# MainSchematic_F1.net
KiCad netlist of a schematic drawn in EAGLE
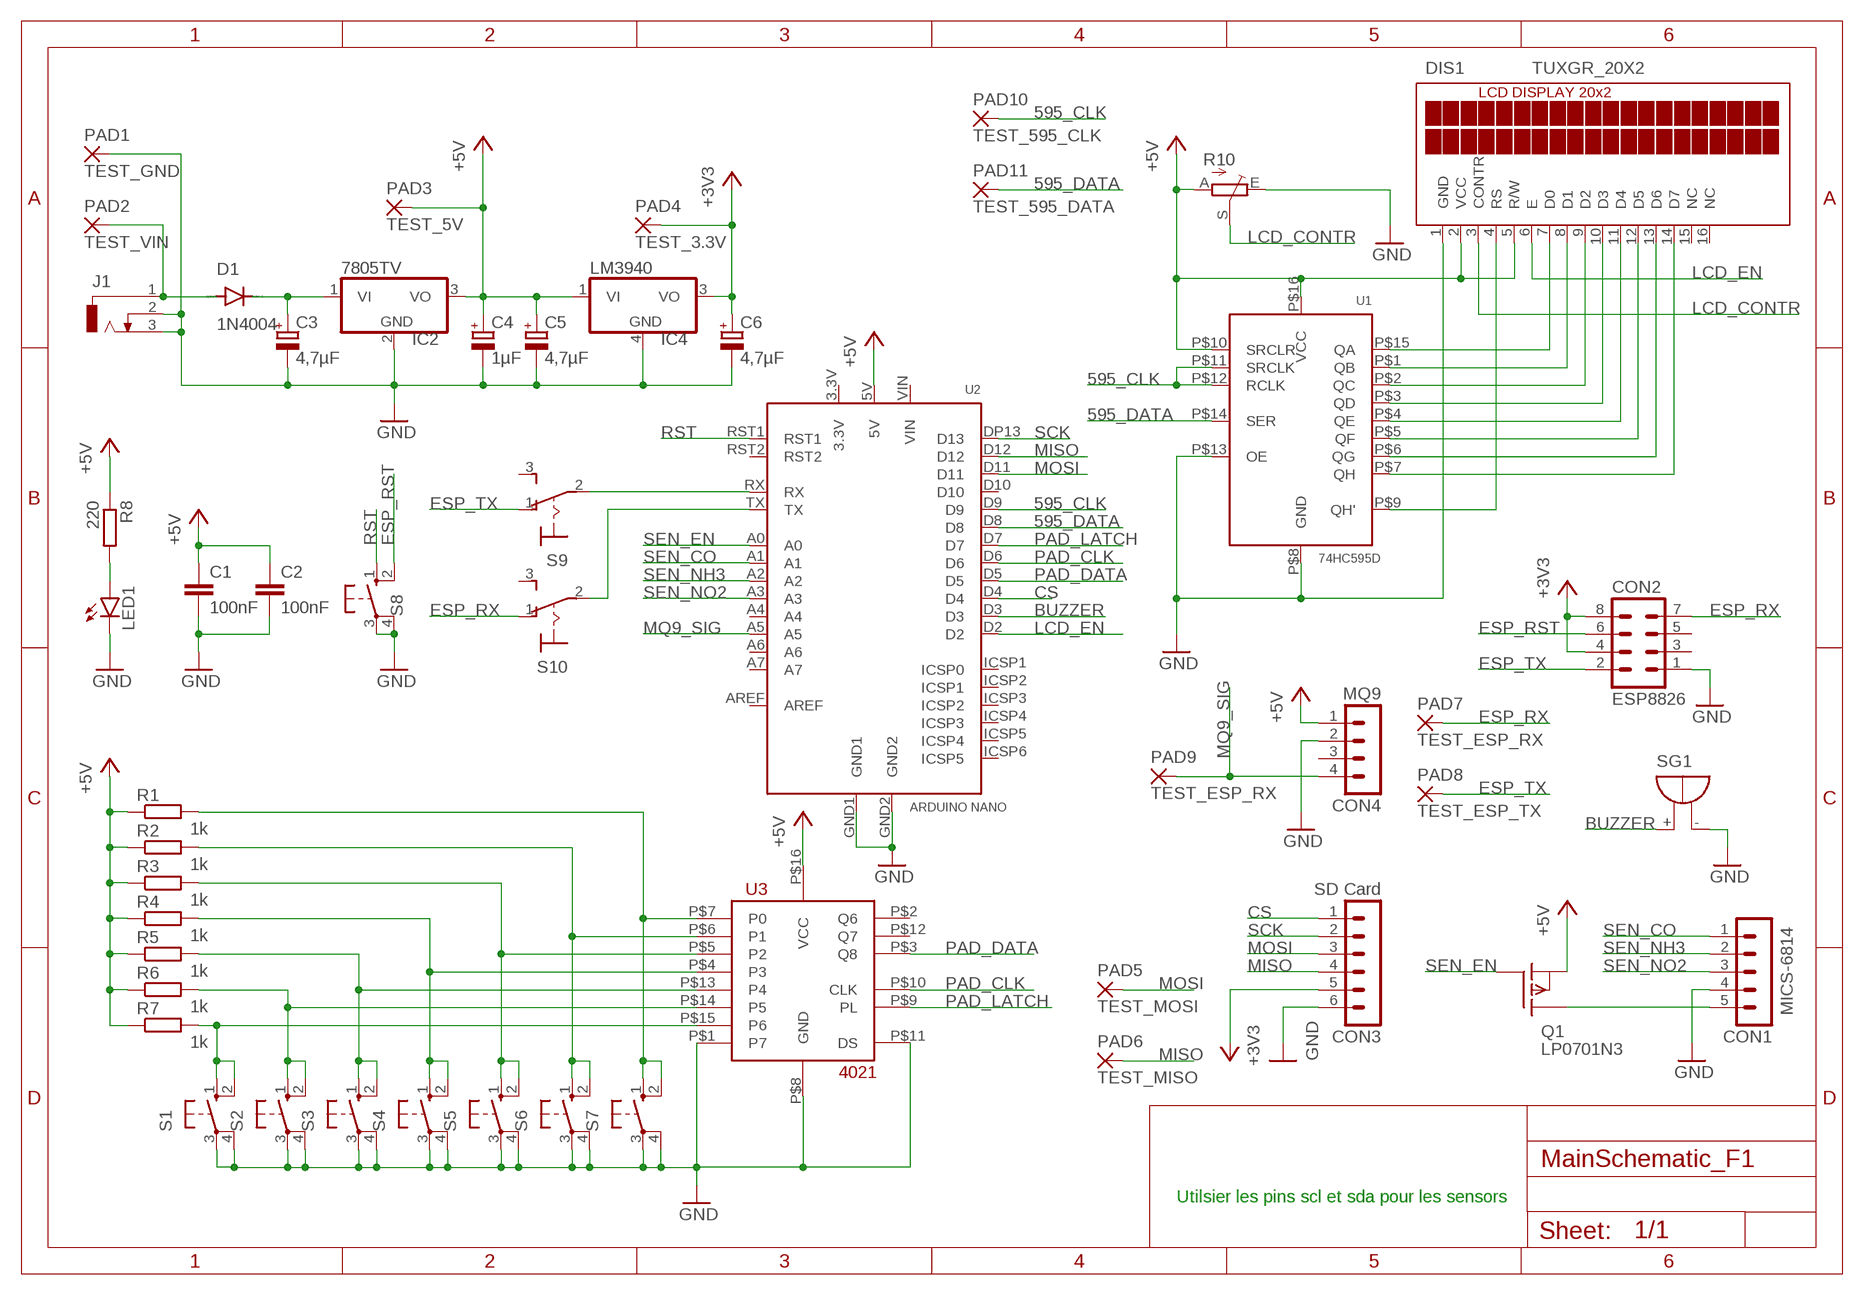
[diagram p0: schematic, sheet 1]

(export (version "E")
  (design (tool "Eeschema 10.0.6"))
  (components
    (comp (ref "C1")
      (value "100nF")
      (footprint "eagle-import:C5B2.5")
      (libsource (lib "eagle-import") (part "C5/2.5"))
    )
    (comp (ref "C2")
      (value "100nF")
      (footprint "eagle-import:C5B2.5")
      (libsource (lib "eagle-import") (part "C5/2.5"))
    )
    (comp (ref "C3")
      (value "4,7µF")
      (footprint "eagle-import:E2,5-6E")
      (libsource (lib "eagle-import") (part "CPOL-EUE2,5-6E"))
    )
    (comp (ref "C4")
      (value "1µF")
      (footprint "eagle-import:E2,5-6E")
      (libsource (lib "eagle-import") (part "CPOL-EUE2,5-6E"))
    )
    (comp (ref "C5")
      (value "4,7µF")
      (footprint "eagle-import:E2,5-6E")
      (libsource (lib "eagle-import") (part "CPOL-EUE2,5-6E"))
    )
    (comp (ref "C6")
      (value "4,7µF")
      (footprint "eagle-import:E2,5-6E")
      (libsource (lib "eagle-import") (part "CPOL-EUE2,5-6E"))
    )
    (comp (ref "CON1")
      (value "MICS-6814")
      (footprint "eagle-import:MA05-1")
      (libsource (lib "eagle-import") (part "MA05-1"))
    )
    (comp (ref "CON2")
      (value "ESP8826")
      (footprint "eagle-import:MA04-2")
      (libsource (lib "eagle-import") (part "MA04-2"))
    )
    (comp (ref "CON3")
      (value "SD Card")
      (footprint "eagle-import:MA06-1")
      (libsource (lib "eagle-import") (part "MA06-1"))
    )
    (comp (ref "CON4")
      (value "MQ9")
      (footprint "eagle-import:MA04-1")
      (libsource (lib "eagle-import") (part "MA04-1"))
    )
    (comp (ref "D1")
      (value "1N4004")
      (footprint "eagle-import:DO41-10")
      (libsource (lib "eagle-import") (part "1N4004"))
    )
    (comp (ref "DIS1")
      (value "TUXGR_20X2")
      (footprint "eagle-import:TUXGR_20X2")
      (libsource (lib "eagle-import") (part "TUXGR_20X2"))
    )
    (comp (ref "IC2")
      (value "7805TV")
      (footprint "eagle-import:TO220V")
      (libsource (lib "eagle-import") (part "78TV05"))
    )
    (comp (ref "IC4")
      (value "LM3940")
      (footprint "eagle-import:SOT223")
      (libsource (lib "eagle-import") (part "LM340?-MP05"))
    )
    (comp (ref "J1")
      (value "DCJ0303")
      (footprint "eagle-import:DCJ0303")
      (libsource (lib "eagle-import") (part "DCJ0303"))
    )
    (comp (ref "LED1")
      (value "LED3MM")
      (footprint "eagle-import:LED3MM")
      (libsource (lib "eagle-import") (part "LED3MM"))
    )
    (comp (ref "PAD1")
      (value "TEST_GND")
      (footprint "eagle-import:2,54_0,9")
      (libsource (lib "eagle-import") (part "WIREPAD2,54/0,9"))
    )
    (comp (ref "PAD2")
      (value "TEST_VIN")
      (footprint "eagle-import:2,54_0,9")
      (libsource (lib "eagle-import") (part "WIREPAD2,54/0,9"))
    )
    (comp (ref "PAD3")
      (value "TEST_5V")
      (footprint "eagle-import:2,54_0,9")
      (libsource (lib "eagle-import") (part "WIREPAD2,54/0,9"))
    )
    (comp (ref "PAD4")
      (value "TEST_3.3V")
      (footprint "eagle-import:2,54_0,9")
      (libsource (lib "eagle-import") (part "WIREPAD2,54/0,9"))
    )
    (comp (ref "PAD5")
      (value "TEST_MOSI")
      (footprint "eagle-import:2,54_0,9")
      (libsource (lib "eagle-import") (part "WIREPAD2,54/0,9"))
    )
    (comp (ref "PAD6")
      (value "TEST_MISO")
      (footprint "eagle-import:2,54_0,9")
      (libsource (lib "eagle-import") (part "WIREPAD2,54/0,9"))
    )
    (comp (ref "PAD7")
      (value "TEST_ESP_RX")
      (footprint "eagle-import:2,54_0,9")
      (libsource (lib "eagle-import") (part "WIREPAD2,54/0,9"))
    )
    (comp (ref "PAD8")
      (value "TEST_ESP_TX")
      (footprint "eagle-import:2,54_0,9")
      (libsource (lib "eagle-import") (part "WIREPAD2,54/0,9"))
    )
    (comp (ref "PAD9")
      (value "TEST_ESP_RX")
      (footprint "eagle-import:2,54_0,9")
      (libsource (lib "eagle-import") (part "WIREPAD2,54/0,9"))
    )
    (comp (ref "PAD10")
      (value "TEST_595_CLK")
      (footprint "eagle-import:2,54_0,9")
      (libsource (lib "eagle-import") (part "WIREPAD2,54/0,9"))
    )
    (comp (ref "PAD11")
      (value "TEST_595_DATA")
      (footprint "eagle-import:2,54_0,9")
      (libsource (lib "eagle-import") (part "WIREPAD2,54/0,9"))
    )
    (comp (ref "Q1")
      (value "LP0701N3")
      (footprint "eagle-import:TO-92")
      (libsource (lib "eagle-import") (part "LP0701N3"))
    )
    (comp (ref "R1")
      (value "1k")
      (footprint "eagle-import:0204_7")
      (libsource (lib "eagle-import") (part "R-EU_0204/7"))
    )
    (comp (ref "R2")
      (value "1k")
      (footprint "eagle-import:0204_7")
      (libsource (lib "eagle-import") (part "R-EU_0204/7"))
    )
    (comp (ref "R3")
      (value "1k")
      (footprint "eagle-import:0204_7")
      (libsource (lib "eagle-import") (part "R-EU_0204/7"))
    )
    (comp (ref "R4")
      (value "1k")
      (footprint "eagle-import:0204_7")
      (libsource (lib "eagle-import") (part "R-EU_0204/7"))
    )
    (comp (ref "R5")
      (value "1k")
      (footprint "eagle-import:0204_7")
      (libsource (lib "eagle-import") (part "R-EU_0204/7"))
    )
    (comp (ref "R6")
      (value "1k")
      (footprint "eagle-import:0204_7")
      (libsource (lib "eagle-import") (part "R-EU_0204/7"))
    )
    (comp (ref "R7")
      (value "1k")
      (footprint "eagle-import:0204_7")
      (libsource (lib "eagle-import") (part "R-EU_0204/7"))
    )
    (comp (ref "R8")
      (value "220")
      (footprint "eagle-import:0204_7")
      (libsource (lib "eagle-import") (part "R-EU_0204/7"))
    )
    (comp (ref "R10")
      (value "TRIM_EU-RJ9W")
      (footprint "eagle-import:RJ9W")
      (libsource (lib "eagle-import") (part "TRIM_EU-RJ9W"))
    )
    (comp (ref "S1")
      (value "10-XX")
      (footprint "eagle-import:B3F-10XX")
      (fields (field (name "MPN") "B3F-1000"))
      (libsource (lib "eagle-import") (part "10-XX"))
    )
    (comp (ref "S2")
      (value "10-XX")
      (footprint "eagle-import:B3F-10XX")
      (fields (field (name "MPN") "B3F-1000"))
      (libsource (lib "eagle-import") (part "10-XX"))
    )
    (comp (ref "S3")
      (value "10-XX")
      (footprint "eagle-import:B3F-10XX")
      (fields (field (name "MPN") "B3F-1000"))
      (libsource (lib "eagle-import") (part "10-XX"))
    )
    (comp (ref "S4")
      (value "10-XX")
      (footprint "eagle-import:B3F-10XX")
      (fields (field (name "MPN") "B3F-1000"))
      (libsource (lib "eagle-import") (part "10-XX"))
    )
    (comp (ref "S5")
      (value "10-XX")
      (footprint "eagle-import:B3F-10XX")
      (fields (field (name "MPN") "B3F-1000"))
      (libsource (lib "eagle-import") (part "10-XX"))
    )
    (comp (ref "S6")
      (value "10-XX")
      (footprint "eagle-import:B3F-10XX")
      (fields (field (name "MPN") "B3F-1000"))
      (libsource (lib "eagle-import") (part "10-XX"))
    )
    (comp (ref "S7")
      (value "10-XX")
      (footprint "eagle-import:B3F-10XX")
      (fields (field (name "MPN") "B3F-1000"))
      (libsource (lib "eagle-import") (part "10-XX"))
    )
    (comp (ref "S8")
      (value "10-XX")
      (footprint "eagle-import:B3F-10XX")
      (fields (field (name "MPN") "B3F-1000"))
      (libsource (lib "eagle-import") (part "10-XX"))
    )
    (comp (ref "S9")
      (value "320-916")
      (footprint "eagle-import:320-916")
      (libsource (lib "eagle-import") (part "320-916"))
    )
    (comp (ref "S10")
      (value "320-916")
      (footprint "eagle-import:320-916")
      (libsource (lib "eagle-import") (part "320-916"))
    )
    (comp (ref "SG1")
      (value "F/TMB")
      (footprint "eagle-import:F_TMB")
      (libsource (lib "eagle-import") (part "F/TMB"))
    )
    (comp (ref "U1")
      (value "74HC595D")
      (footprint "eagle-import:SOP-16")
      (libsource (lib "eagle-import") (part "74HC595D_SOP16"))
    )
    (comp (ref "U2")
      (value "ARDUINO NANO")
      (footprint "eagle-import:SOCKET_NANO")
      (libsource (lib "eagle-import") (part "ARDUINO_NANO_SOCKET"))
    )
    (comp (ref "U3")
      (value "4021")
      (footprint "eagle-import:DIP")
      (libsource (lib "eagle-import") (part "4021"))
    )
  )
  (nets
    (net (code "1") (name "+3V3") (class "Default")
      (node (ref "C6") (pin "+") (pinfunction "+_+") (pintype "passive"))
      (node (ref "CON2") (pin "4") (pinfunction "4_4") (pintype "passive"))
      (node (ref "CON2") (pin "8") (pinfunction "8_8") (pintype "passive"))
      (node (ref "CON3") (pin "5") (pinfunction "5_5") (pintype "passive"))
      (node (ref "IC4") (pin "3") (pinfunction "VO_3") (pintype "passive"))
      (node (ref "PAD4") (pin "1") (pinfunction "P_1") (pintype "passive"))
    )
    (net (code "2") (name "+5V") (class "Default")
      (node (ref "C1") (pin "1") (pinfunction "1_1") (pintype "passive"))
      (node (ref "C2") (pin "1") (pinfunction "1_1") (pintype "passive"))
      (node (ref "C4") (pin "+") (pinfunction "+_+") (pintype "passive"))
      (node (ref "C5") (pin "+") (pinfunction "+_+") (pintype "passive"))
      (node (ref "CON4") (pin "1") (pinfunction "1_1") (pintype "passive"))
      (node (ref "DIS1") (pin "2") (pinfunction "VCC_2") (pintype "power_in"))
      (node (ref "DIS1") (pin "5") (pinfunction "R/W_5") (pintype "input"))
      (node (ref "IC2") (pin "3") (pinfunction "VO_3") (pintype "passive"))
      (node (ref "IC4") (pin "1") (pinfunction "VI_1") (pintype "input"))
      (node (ref "PAD3") (pin "1") (pinfunction "P_1") (pintype "passive"))
      (node (ref "Q1") (pin "1") (pinfunction "S_1") (pintype "passive"))
      (node (ref "R1") (pin "1") (pinfunction "1_1") (pintype "passive"))
      (node (ref "R10") (pin "A") (pinfunction "A_A") (pintype "passive"))
      (node (ref "R2") (pin "1") (pinfunction "1_1") (pintype "passive"))
      (node (ref "R3") (pin "1") (pinfunction "1_1") (pintype "passive"))
      (node (ref "R4") (pin "1") (pinfunction "1_1") (pintype "passive"))
      (node (ref "R5") (pin "1") (pinfunction "1_1") (pintype "passive"))
      (node (ref "R6") (pin "1") (pinfunction "1_1") (pintype "passive"))
      (node (ref "R7") (pin "1") (pinfunction "1_1") (pintype "passive"))
      (node (ref "R8") (pin "1") (pinfunction "1_1") (pintype "passive"))
      (node (ref "U1") (pin "P$10") (pinfunction "SRCLR_P$10") (pintype "input"))
      (node (ref "U1") (pin "P$16") (pinfunction "VCC_P$16") (pintype "power_in"))
      (node (ref "U2") (pin "5V") (pinfunction "5V_5V") (pintype "power_in"))
      (node (ref "U3") (pin "P$16") (pinfunction "VCC_P$16") (pintype "power_in"))
    )
    (net (code "3") (name "/3.3V") (class "Default")
      (node (ref "U2") (pin "3.3V") (pinfunction "3.3V_3.3V") (pintype "power_in"))
    )
    (net (code "4") (name "/595_CLK") (class "Default")
      (node (ref "PAD10") (pin "1") (pinfunction "P_1") (pintype "passive"))
      (node (ref "U1") (pin "P$11") (pinfunction "SRCLK_P$11") (pintype "input"))
      (node (ref "U1") (pin "P$12") (pinfunction "RCLK_P$12") (pintype "input"))
      (node (ref "U2") (pin "D9") (pinfunction "D9_D9") (pintype "bidirectional"))
    )
    (net (code "5") (name "/595_DATA") (class "Default")
      (node (ref "PAD11") (pin "1") (pinfunction "P_1") (pintype "passive"))
      (node (ref "U1") (pin "P$14") (pinfunction "SER_P$14") (pintype "input"))
      (node (ref "U2") (pin "D8") (pinfunction "D8_D8") (pintype "bidirectional"))
    )
    (net (code "6") (name "/BUZZER") (class "Default")
      (node (ref "SG1") (pin "+") (pinfunction "+_+") (pintype "passive"))
      (node (ref "U2") (pin "D3") (pinfunction "D3_D3") (pintype "bidirectional"))
    )
    (net (code "7") (name "/CS") (class "Default")
      (node (ref "CON3") (pin "1") (pinfunction "1_1") (pintype "passive"))
      (node (ref "U2") (pin "D4") (pinfunction "D4_D4") (pintype "bidirectional"))
    )
    (net (code "8") (name "/ESP_RST") (class "Default")
      (node (ref "CON2") (pin "6") (pinfunction "6_6") (pintype "passive"))
      (node (ref "S8") (pin "2") (pinfunction "S1_2") (pintype "passive"))
    )
    (net (code "9") (name "/ESP_RX") (class "Default")
      (node (ref "CON2") (pin "7") (pinfunction "7_7") (pintype "passive"))
      (node (ref "PAD7") (pin "1") (pinfunction "P_1") (pintype "passive"))
      (node (ref "S10") (pin "1") (pinfunction "O_1") (pintype "passive"))
    )
    (net (code "10") (name "/ESP_TX") (class "Default")
      (node (ref "CON2") (pin "2") (pinfunction "2_2") (pintype "passive"))
      (node (ref "PAD8") (pin "1") (pinfunction "P_1") (pintype "passive"))
      (node (ref "S9") (pin "1") (pinfunction "O_1") (pintype "passive"))
    )
    (net (code "11") (name "/LCD_CONTR") (class "Default")
      (node (ref "DIS1") (pin "3") (pinfunction "CONTR_3") (pintype "input"))
      (node (ref "R10") (pin "S") (pinfunction "S_S") (pintype "passive"))
    )
    (net (code "12") (name "/LCD_EN") (class "Default")
      (node (ref "DIS1") (pin "6") (pinfunction "E_6") (pintype "input"))
      (node (ref "U2") (pin "D2") (pinfunction "D2_D2") (pintype "bidirectional"))
    )
    (net (code "13") (name "/MISO") (class "Default")
      (node (ref "CON3") (pin "4") (pinfunction "4_4") (pintype "passive"))
      (node (ref "PAD6") (pin "1") (pinfunction "P_1") (pintype "passive"))
      (node (ref "U2") (pin "D12") (pinfunction "D12_D12") (pintype "bidirectional"))
    )
    (net (code "14") (name "/MOSI") (class "Default")
      (node (ref "CON3") (pin "3") (pinfunction "3_3") (pintype "passive"))
      (node (ref "PAD5") (pin "1") (pinfunction "P_1") (pintype "passive"))
      (node (ref "U2") (pin "D11") (pinfunction "D11_D11") (pintype "bidirectional"))
    )
    (net (code "15") (name "/MQ9_SIG") (class "Default")
      (node (ref "CON4") (pin "4") (pinfunction "4_4") (pintype "passive"))
      (node (ref "PAD9") (pin "1") (pinfunction "P_1") (pintype "passive"))
      (node (ref "U2") (pin "A5") (pinfunction "A5_A5") (pintype "bidirectional"))
    )
    (net (code "16") (name "/PAD_CLK") (class "Default")
      (node (ref "U2") (pin "D6") (pinfunction "D6_D6") (pintype "bidirectional"))
      (node (ref "U3") (pin "P$10") (pinfunction "CLK_P$10") (pintype "bidirectional"))
    )
    (net (code "17") (name "/PAD_DATA") (class "Default")
      (node (ref "U2") (pin "D5") (pinfunction "D5_D5") (pintype "bidirectional"))
      (node (ref "U3") (pin "P$3") (pinfunction "Q8_P$3") (pintype "bidirectional"))
    )
    (net (code "18") (name "/PAD_LATCH") (class "Default")
      (node (ref "U2") (pin "D7") (pinfunction "D7_D7") (pintype "bidirectional"))
      (node (ref "U3") (pin "P$9") (pinfunction "PL_P$9") (pintype "bidirectional"))
    )
    (net (code "19") (name "/RST") (class "Default")
      (node (ref "S8") (pin "1") (pinfunction "S_1") (pintype "passive"))
      (node (ref "U2") (pin "RST1") (pinfunction "RST1_RST1") (pintype "bidirectional"))
    )
    (net (code "20") (name "/SCK") (class "Default")
      (node (ref "CON3") (pin "2") (pinfunction "2_2") (pintype "passive"))
      (node (ref "U2") (pin "DP13") (pinfunction "D13_DP13") (pintype "bidirectional"))
    )
    (net (code "21") (name "/SEN_CO") (class "Default")
      (node (ref "CON1") (pin "1") (pinfunction "1_1") (pintype "passive"))
      (node (ref "U2") (pin "A1") (pinfunction "A1_A1") (pintype "bidirectional"))
    )
    (net (code "22") (name "/SEN_EN") (class "Default")
      (node (ref "Q1") (pin "2") (pinfunction "G_2") (pintype "passive"))
      (node (ref "U2") (pin "A0") (pinfunction "A0_A0") (pintype "bidirectional"))
    )
    (net (code "23") (name "/SEN_NH3") (class "Default")
      (node (ref "CON1") (pin "2") (pinfunction "2_2") (pintype "passive"))
      (node (ref "U2") (pin "A2") (pinfunction "A2_A2") (pintype "bidirectional"))
    )
    (net (code "24") (name "/SEN_NO2") (class "Default")
      (node (ref "CON1") (pin "3") (pinfunction "3_3") (pintype "passive"))
      (node (ref "U2") (pin "A3") (pinfunction "A3_A3") (pintype "bidirectional"))
    )
    (net (code "25") (name "/VIN") (class "Default")
      (node (ref "U2") (pin "VIN") (pinfunction "VIN_VIN") (pintype "power_in"))
    )
    (net (code "26") (name "GND") (class "Default")
      (node (ref "C1") (pin "2") (pinfunction "2_2") (pintype "passive"))
      (node (ref "C2") (pin "2") (pinfunction "2_2") (pintype "passive"))
      (node (ref "C3") (pin "-") (pinfunction "-_-") (pintype "passive"))
      (node (ref "C4") (pin "-") (pinfunction "-_-") (pintype "passive"))
      (node (ref "C5") (pin "-") (pinfunction "-_-") (pintype "passive"))
      (node (ref "C6") (pin "-") (pinfunction "-_-") (pintype "passive"))
      (node (ref "CON1") (pin "4") (pinfunction "4_4") (pintype "passive"))
      (node (ref "CON2") (pin "1") (pinfunction "1_1") (pintype "passive"))
      (node (ref "CON3") (pin "6") (pinfunction "6_6") (pintype "passive"))
      (node (ref "CON4") (pin "2") (pinfunction "2_2") (pintype "passive"))
      (node (ref "DIS1") (pin "1") (pinfunction "GND_1") (pintype "power_in"))
      (node (ref "IC2") (pin "2") (pinfunction "GND_2") (pintype "passive"))
      (node (ref "IC4") (pin "4") (pinfunction "GND_4") (pintype "passive"))
      (node (ref "J1") (pin "2") (pinfunction "2_2") (pintype "passive"))
      (node (ref "J1") (pin "3") (pinfunction "3_3") (pintype "passive"))
      (node (ref "LED1") (pin "K") (pinfunction "C_K") (pintype "passive"))
      (node (ref "PAD1") (pin "1") (pinfunction "P_1") (pintype "passive"))
      (node (ref "R10") (pin "E") (pinfunction "E_E") (pintype "passive"))
      (node (ref "S1") (pin "3") (pinfunction "P_3") (pintype "passive"))
      (node (ref "S1") (pin "4") (pinfunction "P1_4") (pintype "passive"))
      (node (ref "S2") (pin "3") (pinfunction "P_3") (pintype "passive"))
      (node (ref "S2") (pin "4") (pinfunction "P1_4") (pintype "passive"))
      (node (ref "S3") (pin "3") (pinfunction "P_3") (pintype "passive"))
      (node (ref "S3") (pin "4") (pinfunction "P1_4") (pintype "passive"))
      (node (ref "S4") (pin "3") (pinfunction "P_3") (pintype "passive"))
      (node (ref "S4") (pin "4") (pinfunction "P1_4") (pintype "passive"))
      (node (ref "S5") (pin "3") (pinfunction "P_3") (pintype "passive"))
      (node (ref "S5") (pin "4") (pinfunction "P1_4") (pintype "passive"))
      (node (ref "S6") (pin "3") (pinfunction "P_3") (pintype "passive"))
      (node (ref "S6") (pin "4") (pinfunction "P1_4") (pintype "passive"))
      (node (ref "S7") (pin "3") (pinfunction "P_3") (pintype "passive"))
      (node (ref "S7") (pin "4") (pinfunction "P1_4") (pintype "passive"))
      (node (ref "S8") (pin "3") (pinfunction "P_3") (pintype "passive"))
      (node (ref "S8") (pin "4") (pinfunction "P1_4") (pintype "passive"))
      (node (ref "SG1") (pin "-") (pinfunction "-_-") (pintype "passive"))
      (node (ref "U1") (pin "P$13") (pinfunction "OE_P$13") (pintype "input"))
      (node (ref "U1") (pin "P$8") (pinfunction "GND_P$8") (pintype "power_in"))
      (node (ref "U2") (pin "GND1") (pinfunction "GND1_GND1") (pintype "power_in"))
      (node (ref "U2") (pin "GND2") (pinfunction "GND2_GND2") (pintype "power_in"))
      (node (ref "U3") (pin "P$1") (pinfunction "P7_P$1") (pintype "input"))
      (node (ref "U3") (pin "P$11") (pinfunction "DS_P$11") (pintype "bidirectional"))
      (node (ref "U3") (pin "P$8") (pinfunction "GND_P$8") (pintype "power_in"))
    )
    (net (code "27") (name "Net-(DIS1-D0)") (class "Default")
      (node (ref "DIS1") (pin "7") (pinfunction "D0_7") (pintype "input"))
      (node (ref "U1") (pin "P$15") (pinfunction "QA_P$15") (pintype "output"))
    )
    (net (code "28") (name "Net-(DIS1-D1)") (class "Default")
      (node (ref "DIS1") (pin "8") (pinfunction "D1_8") (pintype "input"))
      (node (ref "U1") (pin "P$1") (pinfunction "QB_P$1") (pintype "output"))
    )
    (net (code "29") (name "Net-(DIS1-D2)") (class "Default")
      (node (ref "DIS1") (pin "9") (pinfunction "D2_9") (pintype "input"))
      (node (ref "U1") (pin "P$2") (pinfunction "QC_P$2") (pintype "output"))
    )
    (net (code "30") (name "Net-(DIS1-D3)") (class "Default")
      (node (ref "DIS1") (pin "10") (pinfunction "D3_10") (pintype "input"))
      (node (ref "U1") (pin "P$3") (pinfunction "QD_P$3") (pintype "output"))
    )
    (net (code "31") (name "Net-(DIS1-D4)") (class "Default")
      (node (ref "DIS1") (pin "11") (pinfunction "D4_11") (pintype "input"))
      (node (ref "U1") (pin "P$4") (pinfunction "QE_P$4") (pintype "output"))
    )
    (net (code "32") (name "Net-(DIS1-D5)") (class "Default")
      (node (ref "DIS1") (pin "12") (pinfunction "D5_12") (pintype "input"))
      (node (ref "U1") (pin "P$5") (pinfunction "QF_P$5") (pintype "output"))
    )
    (net (code "33") (name "Net-(DIS1-D6)") (class "Default")
      (node (ref "DIS1") (pin "13") (pinfunction "D6_13") (pintype "input"))
      (node (ref "U1") (pin "P$6") (pinfunction "QG_P$6") (pintype "output"))
    )
    (net (code "34") (name "Net-(DIS1-D7)") (class "Default")
      (node (ref "DIS1") (pin "14") (pinfunction "D7_14") (pintype "input"))
      (node (ref "U1") (pin "P$7") (pinfunction "QH_P$7") (pintype "output"))
    )
    (net (code "35") (name "Net-(DIS1-RS)") (class "Default")
      (node (ref "DIS1") (pin "4") (pinfunction "RS_4") (pintype "input"))
      (node (ref "U1") (pin "P$9") (pinfunction "QH'_P$9") (pintype "output"))
    )
    (net (code "36") (name "Net-(IC2-VI)") (class "Default")
      (node (ref "C3") (pin "+") (pinfunction "+_+") (pintype "passive"))
      (node (ref "D1") (pin "C") (pinfunction "C_C") (pintype "passive"))
      (node (ref "IC2") (pin "1") (pinfunction "VI_1") (pintype "input"))
    )
    (net (code "37") (name "Net-(LED1-PadA)") (class "Default")
      (node (ref "LED1") (pin "A") (pinfunction "A_A") (pintype "passive"))
      (node (ref "R8") (pin "2") (pinfunction "2_2") (pintype "passive"))
    )
    (net (code "38") (name "Net-(PAD2-P)") (class "Default")
      (node (ref "D1") (pin "A") (pinfunction "A_A") (pintype "passive"))
      (node (ref "J1") (pin "1") (pinfunction "1_1") (pintype "passive"))
      (node (ref "PAD2") (pin "1") (pinfunction "P_1") (pintype "passive"))
    )
    (net (code "39") (name "Net-(Q1-D)") (class "Default")
      (node (ref "CON1") (pin "5") (pinfunction "5_5") (pintype "passive"))
      (node (ref "Q1") (pin "3") (pinfunction "D_3") (pintype "passive"))
    )
    (net (code "40") (name "Net-(S1-S)") (class "Default")
      (node (ref "R7") (pin "2") (pinfunction "2_2") (pintype "passive"))
      (node (ref "S1") (pin "1") (pinfunction "S_1") (pintype "passive"))
      (node (ref "S1") (pin "2") (pinfunction "S1_2") (pintype "passive"))
      (node (ref "U3") (pin "P$15") (pinfunction "P6_P$15") (pintype "bidirectional"))
    )
    (net (code "41") (name "Net-(S2-S)") (class "Default")
      (node (ref "R6") (pin "2") (pinfunction "2_2") (pintype "passive"))
      (node (ref "S2") (pin "1") (pinfunction "S_1") (pintype "passive"))
      (node (ref "S2") (pin "2") (pinfunction "S1_2") (pintype "passive"))
      (node (ref "U3") (pin "P$14") (pinfunction "P5_P$14") (pintype "bidirectional"))
    )
    (net (code "42") (name "Net-(S3-S)") (class "Default")
      (node (ref "R5") (pin "2") (pinfunction "2_2") (pintype "passive"))
      (node (ref "S3") (pin "1") (pinfunction "S_1") (pintype "passive"))
      (node (ref "S3") (pin "2") (pinfunction "S1_2") (pintype "passive"))
      (node (ref "U3") (pin "P$13") (pinfunction "P4_P$13") (pintype "bidirectional"))
    )
    (net (code "43") (name "Net-(S4-S)") (class "Default")
      (node (ref "R4") (pin "2") (pinfunction "2_2") (pintype "passive"))
      (node (ref "S4") (pin "1") (pinfunction "S_1") (pintype "passive"))
      (node (ref "S4") (pin "2") (pinfunction "S1_2") (pintype "passive"))
      (node (ref "U3") (pin "P$4") (pinfunction "P3_P$4") (pintype "bidirectional"))
    )
    (net (code "44") (name "Net-(S5-S)") (class "Default")
      (node (ref "R3") (pin "2") (pinfunction "2_2") (pintype "passive"))
      (node (ref "S5") (pin "1") (pinfunction "S_1") (pintype "passive"))
      (node (ref "S5") (pin "2") (pinfunction "S1_2") (pintype "passive"))
      (node (ref "U3") (pin "P$5") (pinfunction "P2_P$5") (pintype "bidirectional"))
    )
    (net (code "45") (name "Net-(S6-S)") (class "Default")
      (node (ref "R2") (pin "2") (pinfunction "2_2") (pintype "passive"))
      (node (ref "S6") (pin "1") (pinfunction "S_1") (pintype "passive"))
      (node (ref "S6") (pin "2") (pinfunction "S1_2") (pintype "passive"))
      (node (ref "U3") (pin "P$6") (pinfunction "P1_P$6") (pintype "bidirectional"))
    )
    (net (code "46") (name "Net-(S7-S)") (class "Default")
      (node (ref "R1") (pin "2") (pinfunction "2_2") (pintype "passive"))
      (node (ref "S7") (pin "1") (pinfunction "S_1") (pintype "passive"))
      (node (ref "S7") (pin "2") (pinfunction "S1_2") (pintype "passive"))
      (node (ref "U3") (pin "P$7") (pinfunction "P0_P$7") (pintype "bidirectional"))
    )
    (net (code "47") (name "Net-(S9-P)") (class "Default")
      (node (ref "S9") (pin "2") (pinfunction "P_2") (pintype "passive"))
      (node (ref "U2") (pin "RX") (pinfunction "RX_RX") (pintype "bidirectional"))
    )
    (net (code "48") (name "Net-(S10-P)") (class "Default")
      (node (ref "S10") (pin "2") (pinfunction "P_2") (pintype "passive"))
      (node (ref "U2") (pin "TX") (pinfunction "TX_TX") (pintype "bidirectional"))
    )
    (net (code "49") (name "unconnected-(CON2-Pad3)") (class "Default")
      (node (ref "CON2") (pin "3") (pinfunction "3_3") (pintype "passive"))
    )
    (net (code "50") (name "unconnected-(CON2-Pad5)") (class "Default")
      (node (ref "CON2") (pin "5") (pinfunction "5_5") (pintype "passive"))
    )
    (net (code "51") (name "unconnected-(CON4-Pad3)") (class "Default")
      (node (ref "CON4") (pin "3") (pinfunction "3_3") (pintype "passive"))
    )
    (net (code "52") (name "unconnected-(DIS1-NC-Pad15)") (class "Default")
      (node (ref "DIS1") (pin "15") (pinfunction "NC_15") (pintype "no_connect"))
    )
    (net (code "53") (name "unconnected-(DIS1-NC-Pad16)") (class "Default")
      (node (ref "DIS1") (pin "16") (pinfunction "NC_16") (pintype "no_connect"))
    )
    (net (code "54") (name "unconnected-(S9-S-Pad3)") (class "Default")
      (node (ref "S9") (pin "3") (pinfunction "S_3") (pintype "passive"))
    )
    (net (code "55") (name "unconnected-(S10-S-Pad3)") (class "Default")
      (node (ref "S10") (pin "3") (pinfunction "S_3") (pintype "passive"))
    )
    (net (code "56") (name "unconnected-(U2-ICSP0-PadICSP1)") (class "Default")
      (node (ref "U2") (pin "ICSP1") (pinfunction "ICSP0_ICSP1") (pintype "bidirectional"))
    )
    (net (code "57") (name "unconnected-(U2-ICSP1-PadICSP2)") (class "Default")
      (node (ref "U2") (pin "ICSP2") (pinfunction "ICSP1_ICSP2") (pintype "bidirectional"))
    )
    (net (code "58") (name "unconnected-(U2-ICSP2-PadICSP3)") (class "Default")
      (node (ref "U2") (pin "ICSP3") (pinfunction "ICSP2_ICSP3") (pintype "bidirectional"))
    )
    (net (code "59") (name "unconnected-(U2-ICSP3-PadICSP4)") (class "Default")
      (node (ref "U2") (pin "ICSP4") (pinfunction "ICSP3_ICSP4") (pintype "bidirectional"))
    )
    (net (code "60") (name "unconnected-(U2-ICSP4-PadICSP5)") (class "Default")
      (node (ref "U2") (pin "ICSP5") (pinfunction "ICSP4_ICSP5") (pintype "bidirectional"))
    )
    (net (code "61") (name "unconnected-(U2-ICSP5-PadICSP6)") (class "Default")
      (node (ref "U2") (pin "ICSP6") (pinfunction "ICSP5_ICSP6") (pintype "bidirectional"))
    )
    (net (code "62") (name "unconnected-(U2-PadA4)") (class "Default")
      (node (ref "U2") (pin "A4") (pinfunction "A4_A4") (pintype "bidirectional"))
    )
    (net (code "63") (name "unconnected-(U2-PadA6)") (class "Default")
      (node (ref "U2") (pin "A6") (pinfunction "A6_A6") (pintype "bidirectional"))
    )
    (net (code "64") (name "unconnected-(U2-PadA7)") (class "Default")
      (node (ref "U2") (pin "A7") (pinfunction "A7_A7") (pintype "bidirectional"))
    )
    (net (code "65") (name "unconnected-(U2-PadAREF)") (class "Default")
      (node (ref "U2") (pin "AREF") (pinfunction "AREF_AREF") (pintype "bidirectional"))
    )
    (net (code "66") (name "unconnected-(U2-PadD10)") (class "Default")
      (node (ref "U2") (pin "D10") (pinfunction "D10_D10") (pintype "bidirectional"))
    )
    (net (code "67") (name "unconnected-(U2-PadRST2)") (class "Default")
      (node (ref "U2") (pin "RST2") (pinfunction "RST2_RST2") (pintype "bidirectional"))
    )
    (net (code "68") (name "unconnected-(U3-Q6-PadP$2)") (class "Default")
      (node (ref "U3") (pin "P$2") (pinfunction "Q6_P$2") (pintype "bidirectional"))
    )
    (net (code "69") (name "unconnected-(U3-Q7-PadP$12)") (class "Default")
      (node (ref "U3") (pin "P$12") (pinfunction "Q7_P$12") (pintype "bidirectional"))
    )
  )
)
